# SIG_IN.net
KiCad netlist of a schematic drawn in Altium Designer
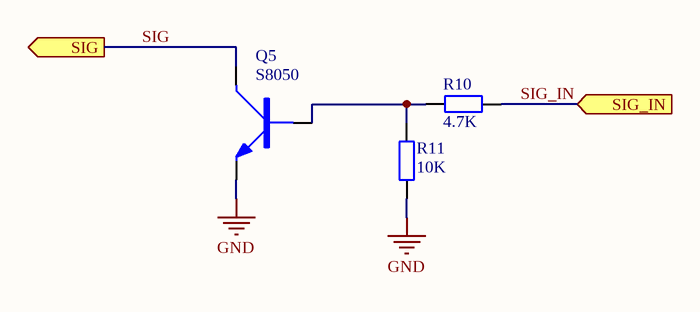
[diagram p0: SIG_IN.SchDoc]

(export (version "E")
  (design (tool "Eeschema 10.0.6"))
  (components
    (comp (ref "Q5")
      (value "S8050")
      (footprint "SOT-23")
      (description "NPN三极管")
      (libsource (lib "三极管") (part "NPN"))
    )
    (comp (ref "R10")
      (value "4.7K")
      (footprint "R 0603")
      (description "贴片电阻")
      (fields (field (name "版权归属") "源创客"))
      (libsource (lib "源创客") (part "R"))
    )
    (comp (ref "R11")
      (value "10K")
      (footprint "R 0603")
      (description "贴片电阻")
      (fields (field (name "版权归属") "源创客"))
      (libsource (lib "源创客") (part "R"))
    )
  )
  (nets
    (net (code "1") (name "/SIG") (class "Default")
      (node (ref "Q5") (pin "C") (pinfunction "C_C") (pintype "passive"))
    )
    (net (code "2") (name "/SIG_IN") (class "Default")
      (node (ref "R10") (pin "2") (pinfunction "2_2") (pintype "passive"))
    )
    (net (code "3") (name "GND") (class "Default")
      (node (ref "Q5") (pin "E") (pinfunction "E_E") (pintype "passive"))
      (node (ref "R11") (pin "1") (pinfunction "1_1") (pintype "passive"))
    )
    (net (code "4") (name "Net-(Q5-PadB)") (class "Default")
      (node (ref "Q5") (pin "B") (pinfunction "B_B") (pintype "passive"))
      (node (ref "R10") (pin "1") (pinfunction "1_1") (pintype "passive"))
      (node (ref "R11") (pin "2") (pinfunction "2_2") (pintype "passive"))
    )
  )
)
